# servos_schematic.net
KiCad netlist of a schematic drawn in EAGLE
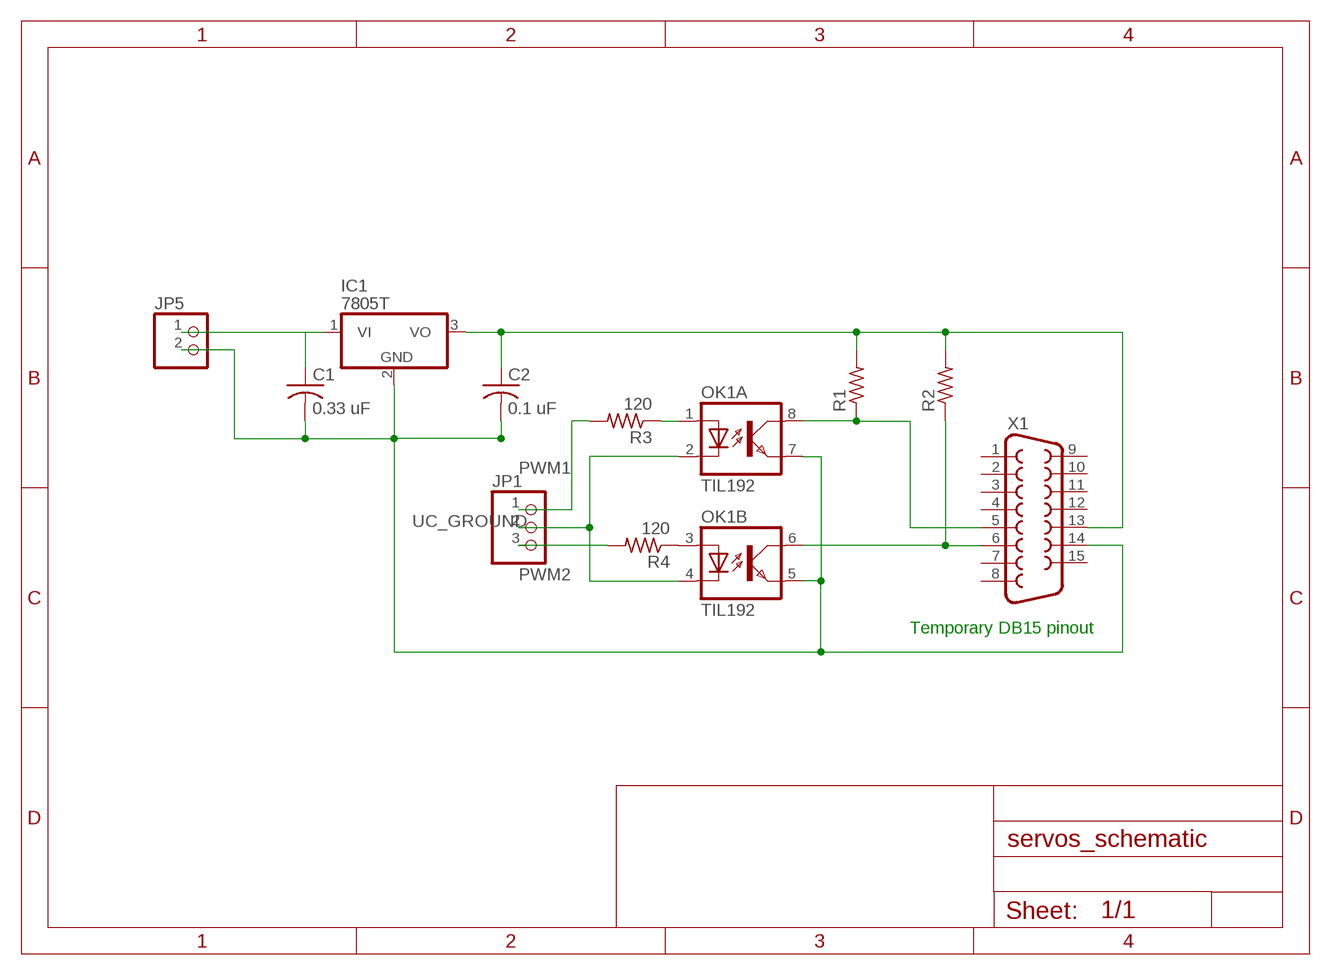
[diagram p0: schematic, sheet 1]

(export (version "E")
  (design (tool "Eeschema 10.0.6"))
  (components
    (comp (ref "C1")
      (value "0.33 uF")
      (footprint "eagle-import:C025-050X050")
      (libsource (lib "eagle-import") (part "C-US025-050X050"))
    )
    (comp (ref "C2")
      (value "0.1 uF")
      (footprint "eagle-import:C025-050X050")
      (libsource (lib "eagle-import") (part "C-US025-050X050"))
    )
    (comp (ref "IC1")
      (value "7805T")
      (footprint "eagle-import:TO220H")
      (libsource (lib "eagle-import") (part "78T05"))
    )
    (comp (ref "JP1")
      (value "PINHD-1X3")
      (footprint "eagle-import:1X03")
      (libsource (lib "eagle-import") (part "PINHD-1X3"))
    )
    (comp (ref "JP5")
      (value "PINHD-1X2")
      (footprint "eagle-import:1X02")
      (libsource (lib "eagle-import") (part "PINHD-1X2"))
    )
    (comp (ref "OK1")
      (value "TIL192")
      (footprint "eagle-import:DIL08")
      (libsource (lib "eagle-import") (part "TIL192"))
    )
    (comp (ref "R1")
      (value "R-US_0204/5")
      (footprint "eagle-import:0204_5")
      (libsource (lib "eagle-import") (part "R-US_0204/5"))
    )
    (comp (ref "R2")
      (value "R-US_0204/5")
      (footprint "eagle-import:0204_5")
      (libsource (lib "eagle-import") (part "R-US_0204/5"))
    )
    (comp (ref "R3")
      (value "120")
      (footprint "eagle-import:0204_5")
      (libsource (lib "eagle-import") (part "R-US_0204/5"))
    )
    (comp (ref "R4")
      (value "120")
      (footprint "eagle-import:0204_5")
      (libsource (lib "eagle-import") (part "R-US_0204/5"))
    )
    (comp (ref "X1")
      (value "F15H")
      (footprint "eagle-import:F15H")
      (libsource (lib "eagle-import") (part "F15H"))
    )
  )
  (nets
    (net (code "1") (name "/PWM1") (class "Default")
      (node (ref "JP1") (pin "1") (pinfunction "1_1") (pintype "passive"))
      (node (ref "R3") (pin "2") (pinfunction "2_2") (pintype "passive"))
    )
    (net (code "2") (name "/PWM2") (class "Default")
      (node (ref "JP1") (pin "3") (pinfunction "3_3") (pintype "passive"))
      (node (ref "R4") (pin "2") (pinfunction "2_2") (pintype "passive"))
    )
    (net (code "3") (name "/UC_GROUND") (class "Default")
      (node (ref "JP1") (pin "2") (pinfunction "2_2") (pintype "passive"))
      (node (ref "OK1") (pin "2") (pinfunction "C_2") (pintype "passive"))
      (node (ref "OK1") (pin "4") (pinfunction "C_4") (pintype "passive"))
    )
    (net (code "4") (name "Net-(IC1-GND)") (class "Default")
      (node (ref "C1") (pin "2") (pinfunction "2_2") (pintype "passive"))
      (node (ref "C2") (pin "2") (pinfunction "2_2") (pintype "passive"))
      (node (ref "IC1") (pin "2") (pinfunction "GND_2") (pintype "passive"))
      (node (ref "JP5") (pin "2") (pinfunction "2_2") (pintype "passive"))
      (node (ref "OK1") (pin "5") (pinfunction "EMIT_5") (pintype "passive"))
      (node (ref "OK1") (pin "7") (pinfunction "EMIT_7") (pintype "passive"))
      (node (ref "X1") (pin "14") (pinfunction "14_14") (pintype "passive"))
    )
    (net (code "5") (name "Net-(IC1-VI)") (class "Default")
      (node (ref "C1") (pin "1") (pinfunction "1_1") (pintype "passive"))
      (node (ref "IC1") (pin "1") (pinfunction "VI_1") (pintype "input"))
      (node (ref "JP5") (pin "1") (pinfunction "1_1") (pintype "passive"))
    )
    (net (code "6") (name "Net-(IC1-VO)") (class "Default")
      (node (ref "C2") (pin "1") (pinfunction "1_1") (pintype "passive"))
      (node (ref "IC1") (pin "3") (pinfunction "VO_3") (pintype "passive"))
      (node (ref "R1") (pin "2") (pinfunction "2_2") (pintype "passive"))
      (node (ref "R2") (pin "2") (pinfunction "2_2") (pintype "passive"))
      (node (ref "X1") (pin "13") (pinfunction "13_13") (pintype "passive"))
    )
    (net (code "7") (name "Net-(OK1A-A)") (class "Default")
      (node (ref "OK1") (pin "1") (pinfunction "A_1") (pintype "passive"))
      (node (ref "R3") (pin "1") (pinfunction "1_1") (pintype "passive"))
    )
    (net (code "8") (name "Net-(OK1A-COL)") (class "Default")
      (node (ref "OK1") (pin "8") (pinfunction "COL_8") (pintype "passive"))
      (node (ref "R1") (pin "1") (pinfunction "1_1") (pintype "passive"))
      (node (ref "X1") (pin "5") (pinfunction "5_5") (pintype "passive"))
    )
    (net (code "9") (name "Net-(OK1B-A)") (class "Default")
      (node (ref "OK1") (pin "3") (pinfunction "A_3") (pintype "passive"))
      (node (ref "R4") (pin "1") (pinfunction "1_1") (pintype "passive"))
    )
    (net (code "10") (name "Net-(OK1B-COL)") (class "Default")
      (node (ref "OK1") (pin "6") (pinfunction "COL_6") (pintype "passive"))
      (node (ref "R2") (pin "1") (pinfunction "1_1") (pintype "passive"))
      (node (ref "X1") (pin "6") (pinfunction "6_6") (pintype "passive"))
    )
    (net (code "11") (name "unconnected-(X1-Pad1)") (class "Default")
      (node (ref "X1") (pin "1") (pinfunction "1_1") (pintype "passive"))
    )
    (net (code "12") (name "unconnected-(X1-Pad2)") (class "Default")
      (node (ref "X1") (pin "2") (pinfunction "2_2") (pintype "passive"))
    )
    (net (code "13") (name "unconnected-(X1-Pad3)") (class "Default")
      (node (ref "X1") (pin "3") (pinfunction "3_3") (pintype "passive"))
    )
    (net (code "14") (name "unconnected-(X1-Pad4)") (class "Default")
      (node (ref "X1") (pin "4") (pinfunction "4_4") (pintype "passive"))
    )
    (net (code "15") (name "unconnected-(X1-Pad7)") (class "Default")
      (node (ref "X1") (pin "7") (pinfunction "7_7") (pintype "passive"))
    )
    (net (code "16") (name "unconnected-(X1-Pad8)") (class "Default")
      (node (ref "X1") (pin "8") (pinfunction "8_8") (pintype "passive"))
    )
    (net (code "17") (name "unconnected-(X1-Pad9)") (class "Default")
      (node (ref "X1") (pin "9") (pinfunction "9_9") (pintype "passive"))
    )
    (net (code "18") (name "unconnected-(X1-Pad10)") (class "Default")
      (node (ref "X1") (pin "10") (pinfunction "10_10") (pintype "passive"))
    )
    (net (code "19") (name "unconnected-(X1-Pad11)") (class "Default")
      (node (ref "X1") (pin "11") (pinfunction "11_11") (pintype "passive"))
    )
    (net (code "20") (name "unconnected-(X1-Pad12)") (class "Default")
      (node (ref "X1") (pin "12") (pinfunction "12_12") (pintype "passive"))
    )
    (net (code "21") (name "unconnected-(X1-Pad15)") (class "Default")
      (node (ref "X1") (pin "15") (pinfunction "15_15") (pintype "passive"))
    )
  )
)
